# LockBox_ver1.net
KiCad netlist of a schematic drawn in EAGLE
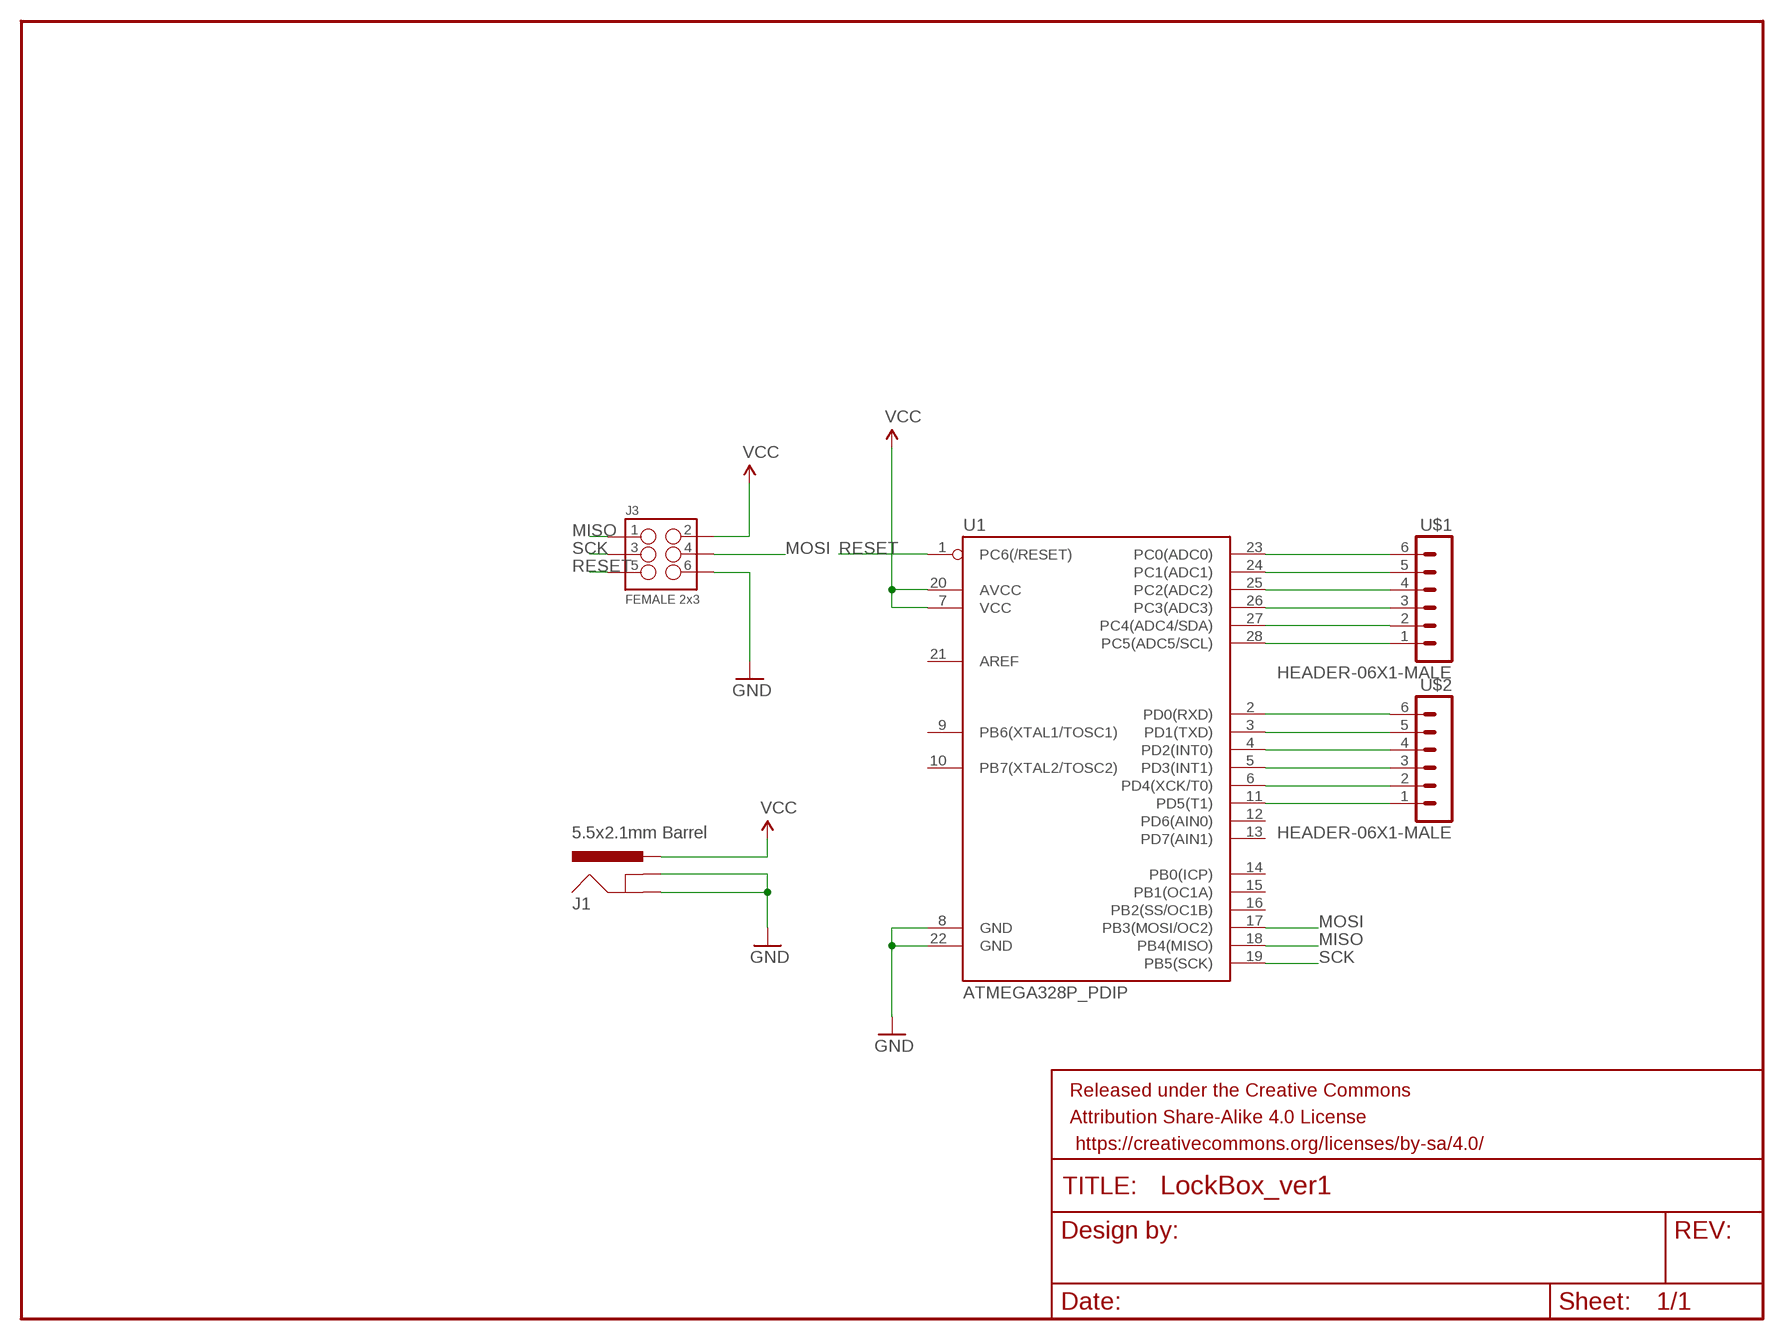
[diagram p0: schematic, sheet 1]

(export (version "E")
  (design (tool "Eeschema 10.0.6"))
  (components
    (comp (ref "FRAME1")
      (value "FRAME-LETTER")
      (footprint "eagle-import:CREATIVE_COMMONS")
      (libsource (lib "eagle-import") (part "FRAME-LETTER"))
    )
    (comp (ref "J1")
      (value "5.5x2.1mm Barrel")
      (footprint "eagle-import:POWER_JACK_SMD")
      (libsource (lib "eagle-import") (part "POWER_JACKSMD"))
    )
    (comp (ref "J3")
      (value "FEMALE 2x3")
      (footprint "eagle-import:2X3")
      (libsource (lib "eagle-import") (part "M03X2FEMALE"))
    )
    (comp (ref "U$1")
      (value "HEADER-06X1-MALE")
      (footprint "eagle-import:06X1-PTH")
      (libsource (lib "eagle-import") (part "HEADER-06X1?-MALE"))
    )
    (comp (ref "U$2")
      (value "HEADER-06X1-MALE")
      (footprint "eagle-import:06X1-PTH")
      (libsource (lib "eagle-import") (part "HEADER-06X1?-MALE"))
    )
    (comp (ref "U1")
      (value "ATMEGA328P_PDIP")
      (footprint "eagle-import:DIL28-3")
      (libsource (lib "eagle-import") (part "ATMEGA328P_PDIP"))
    )
  )
  (nets
    (net (code "1") (name "/MISO") (class "Default")
      (node (ref "J3") (pin "1") (pinfunction "1_1") (pintype "bidirectional"))
      (node (ref "U1") (pin "18") (pinfunction "PB4(MISO)_18") (pintype "bidirectional"))
    )
    (net (code "2") (name "/MOSI") (class "Default")
      (node (ref "J3") (pin "4") (pinfunction "4_4") (pintype "bidirectional"))
      (node (ref "U1") (pin "17") (pinfunction "PB3(MOSI/OC2)_17") (pintype "bidirectional"))
    )
    (net (code "3") (name "/RESET") (class "Default")
      (node (ref "J3") (pin "5") (pinfunction "5_5") (pintype "bidirectional"))
      (node (ref "U1") (pin "1") (pinfunction "PC6(/RESET)_1") (pintype "bidirectional"))
    )
    (net (code "4") (name "/SCK") (class "Default")
      (node (ref "J3") (pin "3") (pinfunction "3_3") (pintype "bidirectional"))
      (node (ref "U1") (pin "19") (pinfunction "PB5(SCK)_19") (pintype "bidirectional"))
    )
    (net (code "5") (name "GND") (class "Default")
      (node (ref "J1") (pin "GND") (pinfunction "GNDBREAK_GND") (pintype "bidirectional"))
      (node (ref "J1") (pin "P$4") (pinfunction "GND_P$4") (pintype "bidirectional"))
      (node (ref "J3") (pin "6") (pinfunction "6_6") (pintype "bidirectional"))
      (node (ref "U1") (pin "22") (pinfunction "GND_22") (pintype "bidirectional"))
      (node (ref "U1") (pin "8") (pinfunction "GND_8") (pintype "bidirectional"))
    )
    (net (code "6") (name "Net-(U1-PC0(ADC0))") (class "Default")
      (node (ref "U$1") (pin "6") (pinfunction "6_6") (pintype "passive"))
      (node (ref "U1") (pin "23") (pinfunction "PC0(ADC0)_23") (pintype "bidirectional"))
    )
    (net (code "7") (name "Net-(U1-PC1(ADC1))") (class "Default")
      (node (ref "U$1") (pin "5") (pinfunction "5_5") (pintype "passive"))
      (node (ref "U1") (pin "24") (pinfunction "PC1(ADC1)_24") (pintype "bidirectional"))
    )
    (net (code "8") (name "Net-(U1-PC2(ADC2))") (class "Default")
      (node (ref "U$1") (pin "4") (pinfunction "4_4") (pintype "passive"))
      (node (ref "U1") (pin "25") (pinfunction "PC2(ADC2)_25") (pintype "bidirectional"))
    )
    (net (code "9") (name "Net-(U1-PC3(ADC3))") (class "Default")
      (node (ref "U$1") (pin "3") (pinfunction "3_3") (pintype "passive"))
      (node (ref "U1") (pin "26") (pinfunction "PC3(ADC3)_26") (pintype "bidirectional"))
    )
    (net (code "10") (name "Net-(U1-PC4(ADC4{slash}SDA))") (class "Default")
      (node (ref "U$1") (pin "2") (pinfunction "2_2") (pintype "passive"))
      (node (ref "U1") (pin "27") (pinfunction "PC4(ADC4/SDA)_27") (pintype "bidirectional"))
    )
    (net (code "11") (name "Net-(U1-PC5(ADC5{slash}SCL))") (class "Default")
      (node (ref "U$1") (pin "1") (pinfunction "1_1") (pintype "passive"))
      (node (ref "U1") (pin "28") (pinfunction "PC5(ADC5/SCL)_28") (pintype "bidirectional"))
    )
    (net (code "12") (name "Net-(U1-PD0(RXD))") (class "Default")
      (node (ref "U$2") (pin "6") (pinfunction "6_6") (pintype "passive"))
      (node (ref "U1") (pin "2") (pinfunction "PD0(RXD)_2") (pintype "bidirectional"))
    )
    (net (code "13") (name "Net-(U1-PD1(TXD))") (class "Default")
      (node (ref "U$2") (pin "5") (pinfunction "5_5") (pintype "passive"))
      (node (ref "U1") (pin "3") (pinfunction "PD1(TXD)_3") (pintype "bidirectional"))
    )
    (net (code "14") (name "Net-(U1-PD2(INT0))") (class "Default")
      (node (ref "U$2") (pin "4") (pinfunction "4_4") (pintype "passive"))
      (node (ref "U1") (pin "4") (pinfunction "PD2(INT0)_4") (pintype "bidirectional"))
    )
    (net (code "15") (name "Net-(U1-PD3(INT1))") (class "Default")
      (node (ref "U$2") (pin "3") (pinfunction "3_3") (pintype "passive"))
      (node (ref "U1") (pin "5") (pinfunction "PD3(INT1)_5") (pintype "bidirectional"))
    )
    (net (code "16") (name "Net-(U1-PD4(XCK{slash}T0))") (class "Default")
      (node (ref "U$2") (pin "2") (pinfunction "2_2") (pintype "passive"))
      (node (ref "U1") (pin "6") (pinfunction "PD4(XCK/T0)_6") (pintype "bidirectional"))
    )
    (net (code "17") (name "Net-(U1-PD5(T1))") (class "Default")
      (node (ref "U$2") (pin "1") (pinfunction "1_1") (pintype "passive"))
      (node (ref "U1") (pin "11") (pinfunction "PD5(T1)_11") (pintype "bidirectional"))
    )
    (net (code "18") (name "VCC") (class "Default")
      (node (ref "J1") (pin "VIN0") (pinfunction "PWR_VIN0") (pintype "bidirectional"))
      (node (ref "J3") (pin "2") (pinfunction "2_2") (pintype "bidirectional"))
      (node (ref "U1") (pin "20") (pinfunction "AVCC_20") (pintype "bidirectional"))
      (node (ref "U1") (pin "7") (pinfunction "VCC_7") (pintype "bidirectional"))
    )
    (net (code "19") (name "unconnected-(U1-AREF-Pad21)") (class "Default")
      (node (ref "U1") (pin "21") (pinfunction "AREF_21") (pintype "bidirectional"))
    )
    (net (code "20") (name "unconnected-(U1-PB0(ICP)-Pad14)") (class "Default")
      (node (ref "U1") (pin "14") (pinfunction "PB0(ICP)_14") (pintype "bidirectional"))
    )
    (net (code "21") (name "unconnected-(U1-PB1(OC1A)-Pad15)") (class "Default")
      (node (ref "U1") (pin "15") (pinfunction "PB1(OC1A)_15") (pintype "bidirectional"))
    )
    (net (code "22") (name "unconnected-(U1-PB2(SS{slash}OC1B)-Pad16)") (class "Default")
      (node (ref "U1") (pin "16") (pinfunction "PB2(SS/OC1B)_16") (pintype "bidirectional"))
    )
    (net (code "23") (name "unconnected-(U1-PB6(XTAL1{slash}TOSC1)-Pad9)") (class "Default")
      (node (ref "U1") (pin "9") (pinfunction "PB6(XTAL1/TOSC1)_9") (pintype "bidirectional"))
    )
    (net (code "24") (name "unconnected-(U1-PB7(XTAL2{slash}TOSC2)-Pad10)") (class "Default")
      (node (ref "U1") (pin "10") (pinfunction "PB7(XTAL2/TOSC2)_10") (pintype "bidirectional"))
    )
    (net (code "25") (name "unconnected-(U1-PD6(AIN0)-Pad12)") (class "Default")
      (node (ref "U1") (pin "12") (pinfunction "PD6(AIN0)_12") (pintype "bidirectional"))
    )
    (net (code "26") (name "unconnected-(U1-PD7(AIN1)-Pad13)") (class "Default")
      (node (ref "U1") (pin "13") (pinfunction "PD7(AIN1)_13") (pintype "bidirectional"))
    )
  )
)
